# IO_EXPAND.net
KiCad netlist of a schematic drawn in Altium Designer
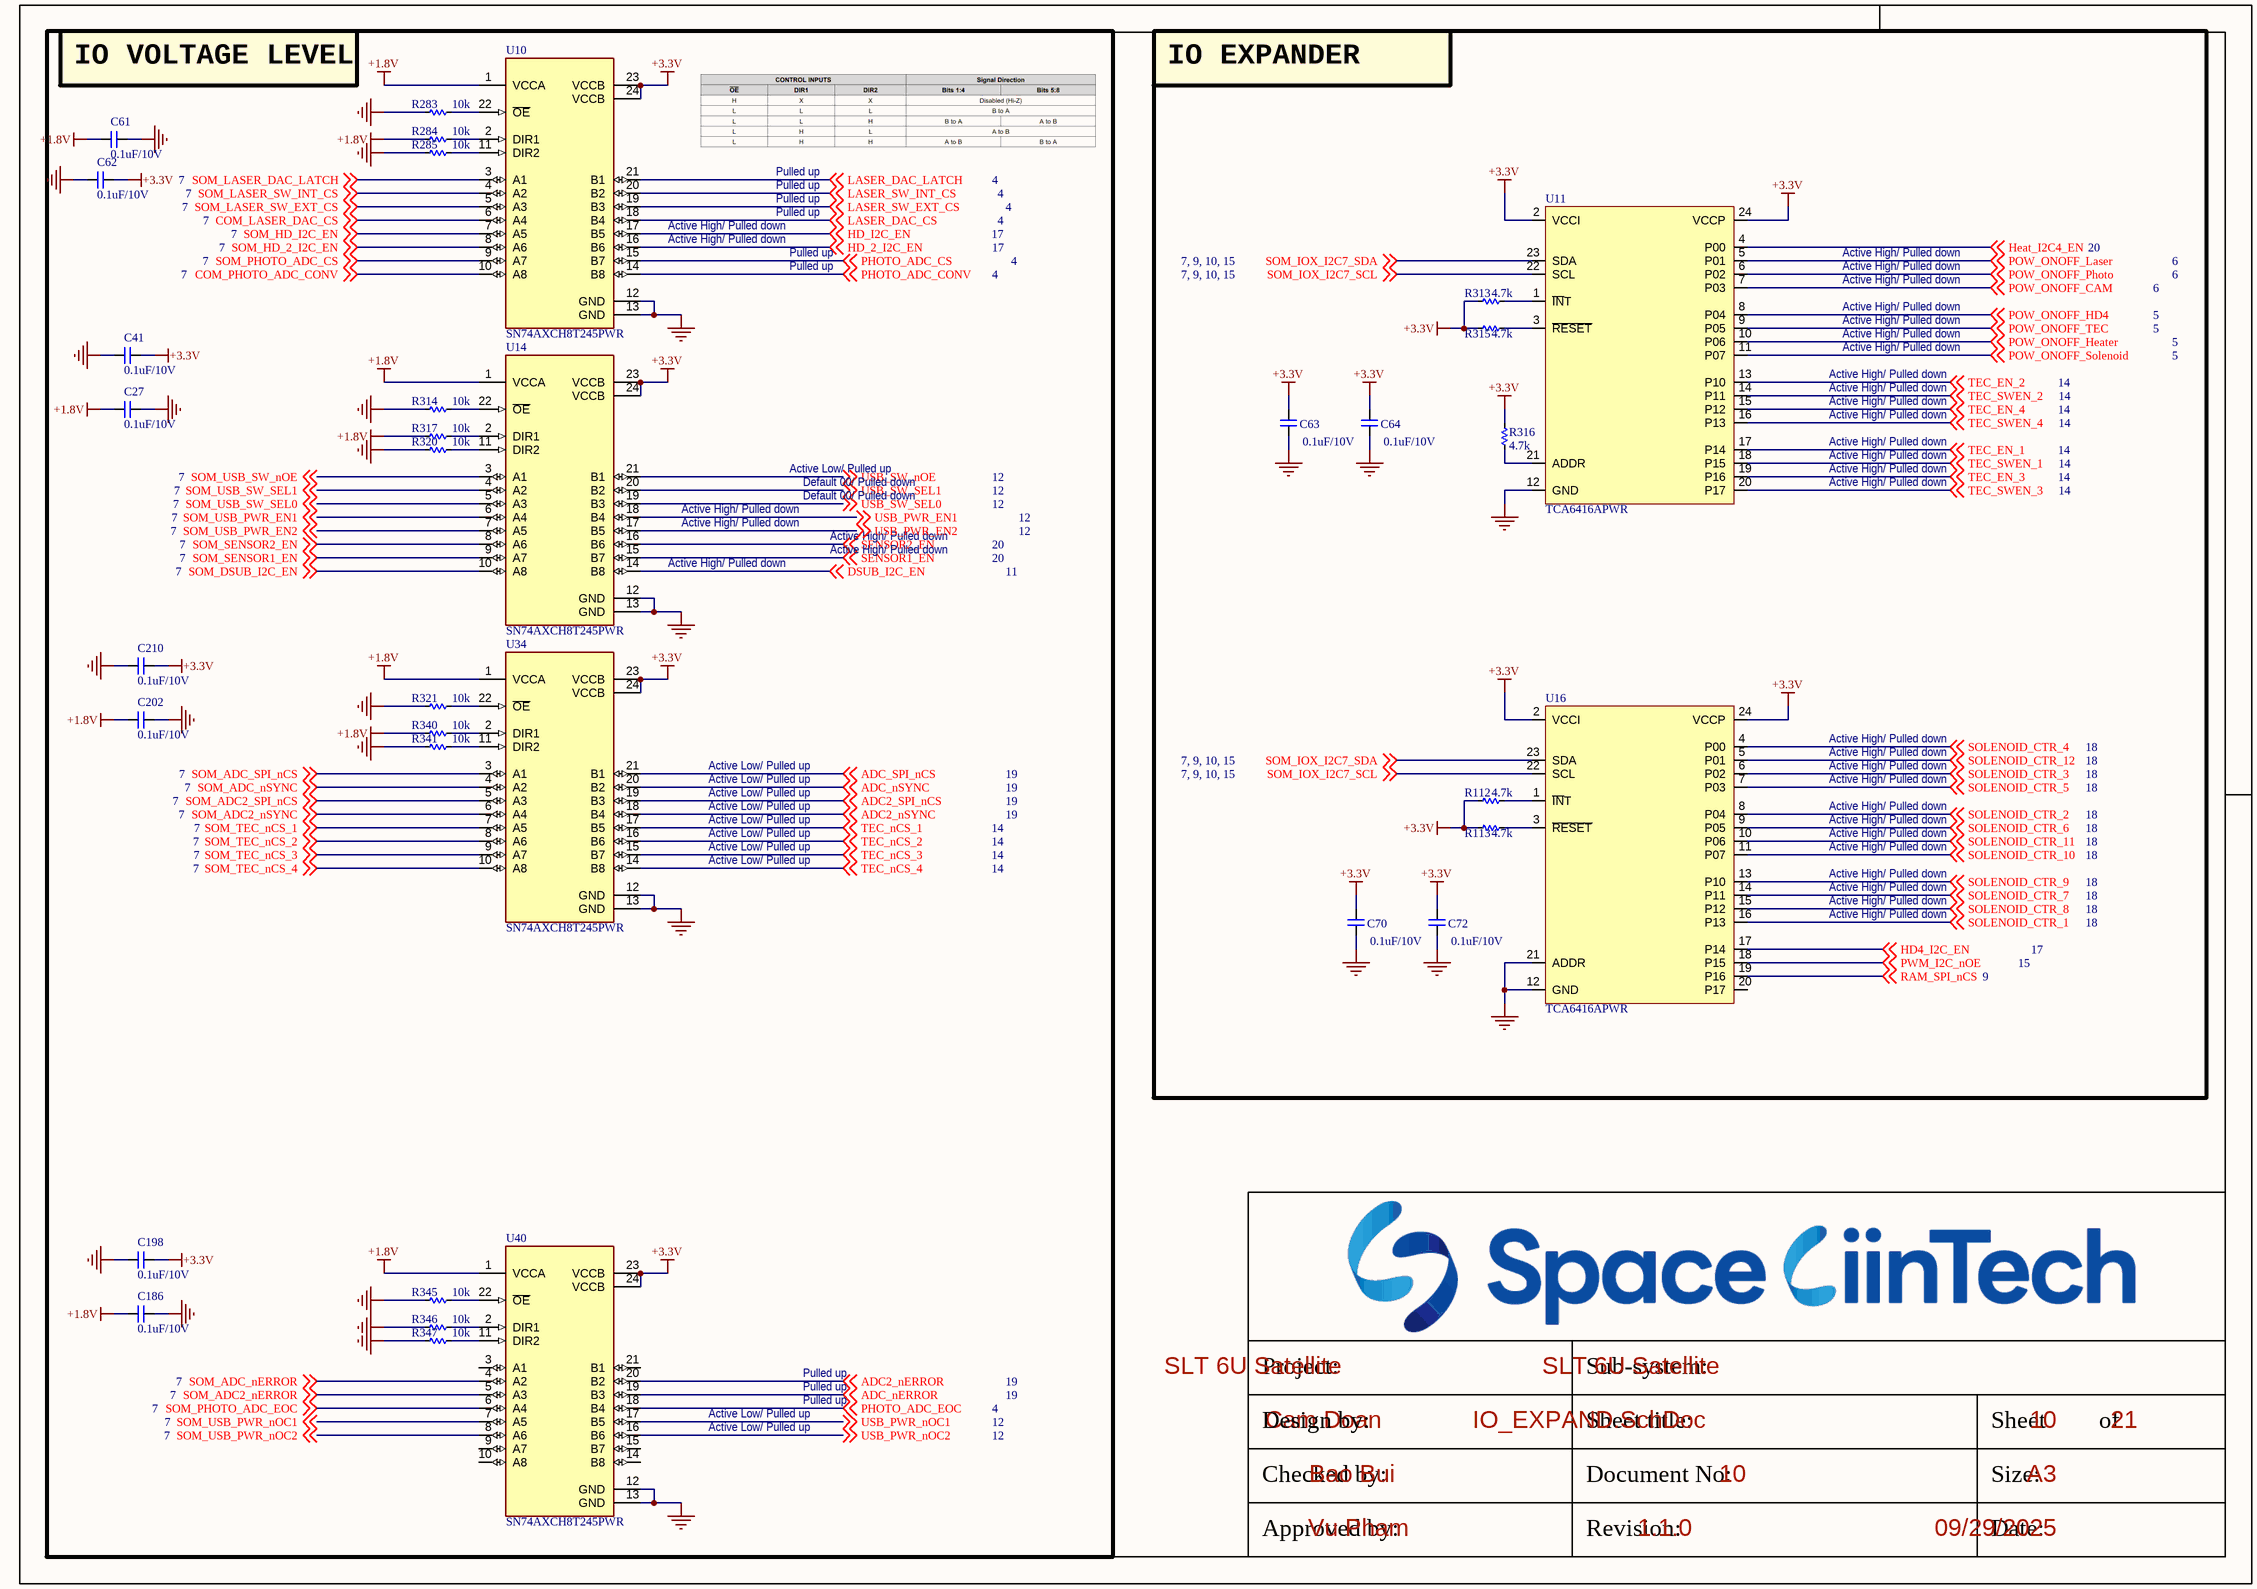
[diagram p0: IO_EXPAND.SchDoc]

(export (version "E")
  (design (tool "Eeschema 10.0.6"))
  (components
    (comp (ref "C27")
      (value "0.1uF/10V")
      (footprint "CAP_C_1005X60")
      (description "CAP CHIP")
      (libsource (lib "LABLIB") (part "_CAP_C_2"))
    )
    (comp (ref "C41")
      (value "0.1uF/10V")
      (footprint "CAP_C_1005X60")
      (description "CAP CHIP")
      (libsource (lib "LABLIB") (part "_CAP_C_2"))
    )
    (comp (ref "C61")
      (value "0.1uF/10V")
      (footprint "CAP_C_1005X60")
      (description "CAP CHIP")
      (libsource (lib "LABLIB") (part "_CAP_C_2"))
    )
    (comp (ref "C62")
      (value "0.1uF/10V")
      (footprint "CAP_C_1005X60")
      (description "CAP CHIP")
      (libsource (lib "LABLIB") (part "_CAP_C_2"))
    )
    (comp (ref "C63")
      (value "0.1uF/10V")
      (footprint "CAP_C_1005X60")
      (description "CAP CHIP")
      (libsource (lib "LABLIB") (part "_CAP_C_2"))
    )
    (comp (ref "C64")
      (value "0.1uF/10V")
      (footprint "CAP_C_1005X60")
      (description "CAP CHIP")
      (libsource (lib "LABLIB") (part "_CAP_C_2"))
    )
    (comp (ref "C70")
      (value "0.1uF/10V")
      (footprint "CAP_C_1005X60")
      (description "CAP CHIP")
      (libsource (lib "LABLIB") (part "_CAP_C_2"))
    )
    (comp (ref "C72")
      (value "0.1uF/10V")
      (footprint "CAP_C_1005X60")
      (description "CAP CHIP")
      (libsource (lib "LABLIB") (part "_CAP_C_2"))
    )
    (comp (ref "C186")
      (value "0.1uF/10V")
      (footprint "CAP_C_1005X60")
      (description "CAP CHIP")
      (libsource (lib "LABLIB") (part "_CAP_C_2"))
    )
    (comp (ref "C198")
      (value "0.1uF/10V")
      (footprint "CAP_C_1005X60")
      (description "CAP CHIP")
      (libsource (lib "LABLIB") (part "_CAP_C_2"))
    )
    (comp (ref "C202")
      (value "0.1uF/10V")
      (footprint "CAP_C_1005X60")
      (description "CAP CHIP")
      (libsource (lib "LABLIB") (part "_CAP_C_2"))
    )
    (comp (ref "C210")
      (value "0.1uF/10V")
      (footprint "CAP_C_1005X60")
      (description "CAP CHIP")
      (libsource (lib "LABLIB") (part "_CAP_C_2"))
    )
    (comp (ref "R112")
      (value "4.7k")
      (footprint "RES_C_1005X40")
      (description "RES")
      (libsource (lib "LABLIB") (part "_RES_B_2"))
    )
    (comp (ref "R113")
      (value "4.7k")
      (footprint "RES_C_1005X40")
      (description "RES")
      (libsource (lib "LABLIB") (part "_RES_B_2"))
    )
    (comp (ref "R283")
      (value "10k")
      (footprint "RES_C_1005X40")
      (description "RES")
      (libsource (lib "LABLIB") (part "_RES_B_2"))
    )
    (comp (ref "R284")
      (value "10k")
      (footprint "RES_C_1005X40")
      (description "RES")
      (libsource (lib "LABLIB") (part "_RES_B_2"))
    )
    (comp (ref "R285")
      (value "10k")
      (footprint "RES_C_1005X40")
      (description "RES")
      (libsource (lib "LABLIB") (part "_RES_B_2"))
    )
    (comp (ref "R313")
      (value "4.7k")
      (footprint "RES_C_1005X40")
      (description "RES")
      (libsource (lib "LABLIB") (part "_RES_B_2"))
    )
    (comp (ref "R314")
      (value "10k")
      (footprint "RES_C_1005X40")
      (description "RES")
      (libsource (lib "LABLIB") (part "_RES_B_2"))
    )
    (comp (ref "R315")
      (value "4.7k")
      (footprint "RES_C_1005X40")
      (description "RES")
      (libsource (lib "LABLIB") (part "_RES_B_2"))
    )
    (comp (ref "R316")
      (value "4.7k")
      (footprint "RES_C_1005X40")
      (description "RES")
      (libsource (lib "LABLIB") (part "_RES_B_2"))
    )
    (comp (ref "R317")
      (value "10k")
      (footprint "RES_C_1005X40")
      (description "RES")
      (libsource (lib "LABLIB") (part "_RES_B_2"))
    )
    (comp (ref "R320")
      (value "10k")
      (footprint "RES_C_1005X40")
      (description "RES")
      (libsource (lib "LABLIB") (part "_RES_B_2"))
    )
    (comp (ref "R321")
      (value "10k")
      (footprint "RES_C_1005X40")
      (description "RES")
      (libsource (lib "LABLIB") (part "_RES_B_2"))
    )
    (comp (ref "R340")
      (value "10k")
      (footprint "RES_C_1005X40")
      (description "RES")
      (libsource (lib "LABLIB") (part "_RES_B_2"))
    )
    (comp (ref "R341")
      (value "10k")
      (footprint "RES_C_1005X40")
      (description "RES")
      (libsource (lib "LABLIB") (part "_RES_B_2"))
    )
    (comp (ref "R345")
      (value "10k")
      (footprint "RES_C_1005X40")
      (description "RES")
      (libsource (lib "LABLIB") (part "_RES_B_2"))
    )
    (comp (ref "R346")
      (value "10k")
      (footprint "RES_C_1005X40")
      (description "RES")
      (libsource (lib "LABLIB") (part "_RES_B_2"))
    )
    (comp (ref "R347")
      (value "10k")
      (footprint "RES_C_1005X40")
      (description "RES")
      (libsource (lib "LABLIB") (part "_RES_B_2"))
    )
    (comp (ref "U10")
      (value "SN74AXCH8T245PWR")
      (footprint "SOP65P640X120-24N")
      (description "8-Bit Dual-Supply Bus Transceiver")
      (fields (field (name "MF") "Texas Instruments"))
      (libsource (lib "LABLIB") (part "IC_voltage_level_SN74AXCH8T245PWR"))
    )
    (comp (ref "U11")
      (value "TCA6416APWR")
      (footprint "SOP65P440W-24N")
      (libsource (lib "CAMERA_SchLib") (part "IC_I2Cto16IO_TCA6416APWR"))
    )
    (comp (ref "U14")
      (value "SN74AXCH8T245PWR")
      (footprint "SOP65P640X120-24N")
      (description "8-Bit Dual-Supply Bus Transceiver")
      (fields (field (name "MF") "Texas Instruments"))
      (libsource (lib "LABLIB") (part "IC_voltage_level_SN74AXCH8T245PWR"))
    )
    (comp (ref "U16")
      (value "TCA6416APWR")
      (footprint "SOP65P440W-24N")
      (libsource (lib "CAMERA_SchLib") (part "IC_I2Cto16IO_TCA6416APWR"))
    )
    (comp (ref "U34")
      (value "SN74AXCH8T245PWR")
      (footprint "SOP65P640X120-24N")
      (description "8-Bit Dual-Supply Bus Transceiver")
      (fields (field (name "MF") "Texas Instruments"))
      (libsource (lib "LABLIB") (part "IC_voltage_level_SN74AXCH8T245PWR"))
    )
    (comp (ref "U40")
      (value "SN74AXCH8T245PWR")
      (footprint "SOP65P640X120-24N")
      (description "8-Bit Dual-Supply Bus Transceiver")
      (fields (field (name "MF") "Texas Instruments"))
      (libsource (lib "LABLIB") (part "IC_voltage_level_SN74AXCH8T245PWR"))
    )
  )
  (nets
    (net (code "1") (name "+1.8V") (class "Default")
      (node (ref "C186") (pin "2") (pinfunction "2_2") (pintype "passive"))
      (node (ref "C202") (pin "2") (pinfunction "2_2") (pintype "passive"))
      (node (ref "C27") (pin "2") (pinfunction "2_2") (pintype "passive"))
      (node (ref "C61") (pin "2") (pinfunction "2_2") (pintype "passive"))
      (node (ref "R284") (pin "2") (pinfunction "2_2") (pintype "passive"))
      (node (ref "R317") (pin "2") (pinfunction "2_2") (pintype "passive"))
      (node (ref "R340") (pin "2") (pinfunction "2_2") (pintype "passive"))
      (node (ref "U10") (pin "1") (pinfunction "VCCA_1") (pintype "power_in"))
      (node (ref "U14") (pin "1") (pinfunction "VCCA_1") (pintype "power_in"))
      (node (ref "U34") (pin "1") (pinfunction "VCCA_1") (pintype "power_in"))
      (node (ref "U40") (pin "1") (pinfunction "VCCA_1") (pintype "power_in"))
    )
    (net (code "2") (name "+3.3V") (class "Default")
      (node (ref "C198") (pin "2") (pinfunction "2_2") (pintype "passive"))
      (node (ref "C210") (pin "2") (pinfunction "2_2") (pintype "passive"))
      (node (ref "C41") (pin "2") (pinfunction "2_2") (pintype "passive"))
      (node (ref "C62") (pin "2") (pinfunction "2_2") (pintype "passive"))
      (node (ref "C63") (pin "2") (pinfunction "2_2") (pintype "passive"))
      (node (ref "C64") (pin "2") (pinfunction "2_2") (pintype "passive"))
      (node (ref "C70") (pin "2") (pinfunction "2_2") (pintype "passive"))
      (node (ref "C72") (pin "2") (pinfunction "2_2") (pintype "passive"))
      (node (ref "R112") (pin "1") (pinfunction "1_1") (pintype "passive"))
      (node (ref "R113") (pin "1") (pinfunction "1_1") (pintype "passive"))
      (node (ref "R313") (pin "1") (pinfunction "1_1") (pintype "passive"))
      (node (ref "R315") (pin "1") (pinfunction "1_1") (pintype "passive"))
      (node (ref "R316") (pin "2") (pinfunction "2_2") (pintype "passive"))
      (node (ref "U10") (pin "23") (pinfunction "VCCB_23") (pintype "power_in"))
      (node (ref "U10") (pin "24") (pinfunction "VCCB_24") (pintype "power_in"))
      (node (ref "U11") (pin "2") (pinfunction "VCCI_2") (pintype "passive"))
      (node (ref "U11") (pin "24") (pinfunction "VCCP_24") (pintype "passive"))
      (node (ref "U14") (pin "23") (pinfunction "VCCB_23") (pintype "power_in"))
      (node (ref "U14") (pin "24") (pinfunction "VCCB_24") (pintype "power_in"))
      (node (ref "U16") (pin "2") (pinfunction "VCCI_2") (pintype "passive"))
      (node (ref "U16") (pin "24") (pinfunction "VCCP_24") (pintype "passive"))
      (node (ref "U34") (pin "23") (pinfunction "VCCB_23") (pintype "power_in"))
      (node (ref "U34") (pin "24") (pinfunction "VCCB_24") (pintype "power_in"))
      (node (ref "U40") (pin "23") (pinfunction "VCCB_23") (pintype "power_in"))
      (node (ref "U40") (pin "24") (pinfunction "VCCB_24") (pintype "power_in"))
    )
    (net (code "3") (name "ADC2_SPI_nCS") (class "Default")
      (node (ref "U34") (pin "19") (pinfunction "B3_19") (pintype "bidirectional"))
    )
    (net (code "4") (name "ADC2_nERROR") (class "Default")
      (node (ref "U40") (pin "20") (pinfunction "B2_20") (pintype "bidirectional"))
    )
    (net (code "5") (name "ADC2_nSYNC") (class "Default")
      (node (ref "U34") (pin "18") (pinfunction "B4_18") (pintype "bidirectional"))
    )
    (net (code "6") (name "ADC_SPI_nCS") (class "Default")
      (node (ref "U34") (pin "21") (pinfunction "B1_21") (pintype "bidirectional"))
    )
    (net (code "7") (name "ADC_nERROR") (class "Default")
      (node (ref "U40") (pin "19") (pinfunction "B3_19") (pintype "bidirectional"))
    )
    (net (code "8") (name "ADC_nSYNC") (class "Default")
      (node (ref "U34") (pin "20") (pinfunction "B2_20") (pintype "bidirectional"))
    )
    (net (code "9") (name "COM_LASER_DAC_CS") (class "Default")
      (node (ref "U10") (pin "6") (pinfunction "A4_6") (pintype "bidirectional"))
    )
    (net (code "10") (name "COM_PHOTO_ADC_CONV") (class "Default")
      (node (ref "U10") (pin "10") (pinfunction "A8_10") (pintype "bidirectional"))
    )
    (net (code "11") (name "DSUB_I2C_EN") (class "Default")
      (node (ref "U14") (pin "14") (pinfunction "B8_14") (pintype "bidirectional"))
    )
    (net (code "12") (name "GND") (class "Default")
      (node (ref "C186") (pin "1") (pinfunction "1_1") (pintype "passive"))
      (node (ref "C198") (pin "1") (pinfunction "1_1") (pintype "passive"))
      (node (ref "C202") (pin "1") (pinfunction "1_1") (pintype "passive"))
      (node (ref "C210") (pin "1") (pinfunction "1_1") (pintype "passive"))
      (node (ref "C27") (pin "1") (pinfunction "1_1") (pintype "passive"))
      (node (ref "C41") (pin "1") (pinfunction "1_1") (pintype "passive"))
      (node (ref "C61") (pin "1") (pinfunction "1_1") (pintype "passive"))
      (node (ref "C62") (pin "1") (pinfunction "1_1") (pintype "passive"))
      (node (ref "C63") (pin "1") (pinfunction "1_1") (pintype "passive"))
      (node (ref "C64") (pin "1") (pinfunction "1_1") (pintype "passive"))
      (node (ref "C70") (pin "1") (pinfunction "1_1") (pintype "passive"))
      (node (ref "C72") (pin "1") (pinfunction "1_1") (pintype "passive"))
      (node (ref "R283") (pin "2") (pinfunction "2_2") (pintype "passive"))
      (node (ref "R285") (pin "2") (pinfunction "2_2") (pintype "passive"))
      (node (ref "R314") (pin "2") (pinfunction "2_2") (pintype "passive"))
      (node (ref "R320") (pin "2") (pinfunction "2_2") (pintype "passive"))
      (node (ref "R321") (pin "2") (pinfunction "2_2") (pintype "passive"))
      (node (ref "R341") (pin "2") (pinfunction "2_2") (pintype "passive"))
      (node (ref "R345") (pin "2") (pinfunction "2_2") (pintype "passive"))
      (node (ref "R346") (pin "2") (pinfunction "2_2") (pintype "passive"))
      (node (ref "R347") (pin "2") (pinfunction "2_2") (pintype "passive"))
      (node (ref "U10") (pin "12") (pinfunction "GND_12") (pintype "power_in"))
      (node (ref "U10") (pin "13") (pinfunction "GND_13") (pintype "power_in"))
      (node (ref "U11") (pin "12") (pinfunction "GND_12") (pintype "passive"))
      (node (ref "U14") (pin "12") (pinfunction "GND_12") (pintype "power_in"))
      (node (ref "U14") (pin "13") (pinfunction "GND_13") (pintype "power_in"))
      (node (ref "U16") (pin "12") (pinfunction "GND_12") (pintype "passive"))
      (node (ref "U16") (pin "21") (pinfunction "ADDR_21") (pintype "passive"))
      (node (ref "U34") (pin "12") (pinfunction "GND_12") (pintype "power_in"))
      (node (ref "U34") (pin "13") (pinfunction "GND_13") (pintype "power_in"))
      (node (ref "U40") (pin "12") (pinfunction "GND_12") (pintype "power_in"))
      (node (ref "U40") (pin "13") (pinfunction "GND_13") (pintype "power_in"))
    )
    (net (code "13") (name "HD4_I2C_EN") (class "Default")
      (node (ref "U16") (pin "17") (pinfunction "P14_17") (pintype "passive"))
    )
    (net (code "14") (name "HD_2_I2C_EN") (class "Default")
      (node (ref "U10") (pin "16") (pinfunction "B6_16") (pintype "bidirectional"))
    )
    (net (code "15") (name "HD_I2C_EN") (class "Default")
      (node (ref "U10") (pin "17") (pinfunction "B5_17") (pintype "bidirectional"))
    )
    (net (code "16") (name "Heat_I2C4_EN") (class "Default")
      (node (ref "U11") (pin "4") (pinfunction "P00_4") (pintype "passive"))
    )
    (net (code "17") (name "LASER_DAC_CS") (class "Default")
      (node (ref "U10") (pin "18") (pinfunction "B4_18") (pintype "bidirectional"))
    )
    (net (code "18") (name "LASER_DAC_LATCH") (class "Default")
      (node (ref "U10") (pin "21") (pinfunction "B1_21") (pintype "bidirectional"))
    )
    (net (code "19") (name "LASER_SW_EXT_CS") (class "Default")
      (node (ref "U10") (pin "19") (pinfunction "B3_19") (pintype "bidirectional"))
    )
    (net (code "20") (name "LASER_SW_INT_CS") (class "Default")
      (node (ref "U10") (pin "20") (pinfunction "B2_20") (pintype "bidirectional"))
    )
    (net (code "21") (name "Net-(U10-DIR1)") (class "Default")
      (node (ref "R284") (pin "1") (pinfunction "1_1") (pintype "passive"))
      (node (ref "U10") (pin "2") (pinfunction "DIR1_2") (pintype "input"))
    )
    (net (code "22") (name "Net-(U10-DIR2)") (class "Default")
      (node (ref "R285") (pin "1") (pinfunction "1_1") (pintype "passive"))
      (node (ref "U10") (pin "11") (pinfunction "DIR2_11") (pintype "input"))
    )
    (net (code "23") (name "Net-(U10-~{OE})") (class "Default")
      (node (ref "R283") (pin "1") (pinfunction "1_1") (pintype "passive"))
      (node (ref "U10") (pin "22") (pinfunction "~{OE}_22") (pintype "input"))
    )
    (net (code "24") (name "Net-(U11-ADDR)") (class "Default")
      (node (ref "R316") (pin "1") (pinfunction "1_1") (pintype "passive"))
      (node (ref "U11") (pin "21") (pinfunction "ADDR_21") (pintype "passive"))
    )
    (net (code "25") (name "Net-(U11-~{IN}T)") (class "Default")
      (node (ref "R313") (pin "2") (pinfunction "2_2") (pintype "passive"))
      (node (ref "U11") (pin "1") (pinfunction "~{IN}T_1") (pintype "passive"))
    )
    (net (code "26") (name "Net-(U11-~{RESET})") (class "Default")
      (node (ref "R315") (pin "2") (pinfunction "2_2") (pintype "passive"))
      (node (ref "U11") (pin "3") (pinfunction "~{RESET}_3") (pintype "passive"))
    )
    (net (code "27") (name "Net-(U14-DIR1)") (class "Default")
      (node (ref "R317") (pin "1") (pinfunction "1_1") (pintype "passive"))
      (node (ref "U14") (pin "2") (pinfunction "DIR1_2") (pintype "input"))
    )
    (net (code "28") (name "Net-(U14-DIR2)") (class "Default")
      (node (ref "R320") (pin "1") (pinfunction "1_1") (pintype "passive"))
      (node (ref "U14") (pin "11") (pinfunction "DIR2_11") (pintype "input"))
    )
    (net (code "29") (name "Net-(U14-~{OE})") (class "Default")
      (node (ref "R314") (pin "1") (pinfunction "1_1") (pintype "passive"))
      (node (ref "U14") (pin "22") (pinfunction "~{OE}_22") (pintype "input"))
    )
    (net (code "30") (name "Net-(U16-~{IN}T)") (class "Default")
      (node (ref "R112") (pin "2") (pinfunction "2_2") (pintype "passive"))
      (node (ref "U16") (pin "1") (pinfunction "~{IN}T_1") (pintype "passive"))
    )
    (net (code "31") (name "Net-(U16-~{RESET})") (class "Default")
      (node (ref "R113") (pin "2") (pinfunction "2_2") (pintype "passive"))
      (node (ref "U16") (pin "3") (pinfunction "~{RESET}_3") (pintype "passive"))
    )
    (net (code "32") (name "Net-(U34-DIR1)") (class "Default")
      (node (ref "R340") (pin "1") (pinfunction "1_1") (pintype "passive"))
      (node (ref "U34") (pin "2") (pinfunction "DIR1_2") (pintype "input"))
    )
    (net (code "33") (name "Net-(U34-DIR2)") (class "Default")
      (node (ref "R341") (pin "1") (pinfunction "1_1") (pintype "passive"))
      (node (ref "U34") (pin "11") (pinfunction "DIR2_11") (pintype "input"))
    )
    (net (code "34") (name "Net-(U34-~{OE})") (class "Default")
      (node (ref "R321") (pin "1") (pinfunction "1_1") (pintype "passive"))
      (node (ref "U34") (pin "22") (pinfunction "~{OE}_22") (pintype "input"))
    )
    (net (code "35") (name "Net-(U40-DIR1)") (class "Default")
      (node (ref "R346") (pin "1") (pinfunction "1_1") (pintype "passive"))
      (node (ref "U40") (pin "2") (pinfunction "DIR1_2") (pintype "input"))
    )
    (net (code "36") (name "Net-(U40-DIR2)") (class "Default")
      (node (ref "R347") (pin "1") (pinfunction "1_1") (pintype "passive"))
      (node (ref "U40") (pin "11") (pinfunction "DIR2_11") (pintype "input"))
    )
    (net (code "37") (name "Net-(U40-~{OE})") (class "Default")
      (node (ref "R345") (pin "1") (pinfunction "1_1") (pintype "passive"))
      (node (ref "U40") (pin "22") (pinfunction "~{OE}_22") (pintype "input"))
    )
    (net (code "38") (name "PHOTO_ADC_CONV") (class "Default")
      (node (ref "U10") (pin "14") (pinfunction "B8_14") (pintype "bidirectional"))
    )
    (net (code "39") (name "PHOTO_ADC_CS") (class "Default")
      (node (ref "U10") (pin "15") (pinfunction "B7_15") (pintype "bidirectional"))
    )
    (net (code "40") (name "PHOTO_ADC_EOC") (class "Default")
      (node (ref "U40") (pin "18") (pinfunction "B4_18") (pintype "bidirectional"))
    )
    (net (code "41") (name "POW_ONOFF_CAM") (class "Default")
      (node (ref "U11") (pin "7") (pinfunction "P03_7") (pintype "passive"))
    )
    (net (code "42") (name "POW_ONOFF_HD4") (class "Default")
      (node (ref "U11") (pin "8") (pinfunction "P04_8") (pintype "passive"))
    )
    (net (code "43") (name "POW_ONOFF_Heater") (class "Default")
      (node (ref "U11") (pin "10") (pinfunction "P06_10") (pintype "passive"))
    )
    (net (code "44") (name "POW_ONOFF_Laser") (class "Default")
      (node (ref "U11") (pin "5") (pinfunction "P01_5") (pintype "passive"))
    )
    (net (code "45") (name "POW_ONOFF_Photo") (class "Default")
      (node (ref "U11") (pin "6") (pinfunction "P02_6") (pintype "passive"))
    )
    (net (code "46") (name "POW_ONOFF_Solenoid") (class "Default")
      (node (ref "U11") (pin "11") (pinfunction "P07_11") (pintype "passive"))
    )
    (net (code "47") (name "POW_ONOFF_TEC") (class "Default")
      (node (ref "U11") (pin "9") (pinfunction "P05_9") (pintype "passive"))
    )
    (net (code "48") (name "PWM_I2C_nOE") (class "Default")
      (node (ref "U16") (pin "18") (pinfunction "P15_18") (pintype "passive"))
    )
    (net (code "49") (name "RAM_SPI_nCS") (class "Default")
      (node (ref "U16") (pin "19") (pinfunction "P16_19") (pintype "passive"))
    )
    (net (code "50") (name "SENSOR1_EN") (class "Default")
      (node (ref "U14") (pin "15") (pinfunction "B7_15") (pintype "bidirectional"))
    )
    (net (code "51") (name "SENSOR2_EN") (class "Default")
      (node (ref "U14") (pin "16") (pinfunction "B6_16") (pintype "bidirectional"))
    )
    (net (code "52") (name "SOLENOID_CTR_1") (class "Default")
      (node (ref "U16") (pin "16") (pinfunction "P13_16") (pintype "passive"))
    )
    (net (code "53") (name "SOLENOID_CTR_2") (class "Default")
      (node (ref "U16") (pin "8") (pinfunction "P04_8") (pintype "passive"))
    )
    (net (code "54") (name "SOLENOID_CTR_3") (class "Default")
      (node (ref "U16") (pin "6") (pinfunction "P02_6") (pintype "passive"))
    )
    (net (code "55") (name "SOLENOID_CTR_4") (class "Default")
      (node (ref "U16") (pin "4") (pinfunction "P00_4") (pintype "passive"))
    )
    (net (code "56") (name "SOLENOID_CTR_5") (class "Default")
      (node (ref "U16") (pin "7") (pinfunction "P03_7") (pintype "passive"))
    )
    (net (code "57") (name "SOLENOID_CTR_6") (class "Default")
      (node (ref "U16") (pin "9") (pinfunction "P05_9") (pintype "passive"))
    )
    (net (code "58") (name "SOLENOID_CTR_7") (class "Default")
      (node (ref "U16") (pin "14") (pinfunction "P11_14") (pintype "passive"))
    )
    (net (code "59") (name "SOLENOID_CTR_8") (class "Default")
      (node (ref "U16") (pin "15") (pinfunction "P12_15") (pintype "passive"))
    )
    (net (code "60") (name "SOLENOID_CTR_9") (class "Default")
      (node (ref "U16") (pin "13") (pinfunction "P10_13") (pintype "passive"))
    )
    (net (code "61") (name "SOLENOID_CTR_10") (class "Default")
      (node (ref "U16") (pin "11") (pinfunction "P07_11") (pintype "passive"))
    )
    (net (code "62") (name "SOLENOID_CTR_11") (class "Default")
      (node (ref "U16") (pin "10") (pinfunction "P06_10") (pintype "passive"))
    )
    (net (code "63") (name "SOLENOID_CTR_12") (class "Default")
      (node (ref "U16") (pin "5") (pinfunction "P01_5") (pintype "passive"))
    )
    (net (code "64") (name "SOM_ADC2_SPI_nCS") (class "Default")
      (node (ref "U34") (pin "5") (pinfunction "A3_5") (pintype "bidirectional"))
    )
    (net (code "65") (name "SOM_ADC2_nERROR") (class "Default")
      (node (ref "U40") (pin "5") (pinfunction "A3_5") (pintype "bidirectional"))
    )
    (net (code "66") (name "SOM_ADC2_nSYNC") (class "Default")
      (node (ref "U34") (pin "6") (pinfunction "A4_6") (pintype "bidirectional"))
    )
    (net (code "67") (name "SOM_ADC_SPI_nCS") (class "Default")
      (node (ref "U34") (pin "3") (pinfunction "A1_3") (pintype "bidirectional"))
    )
    (net (code "68") (name "SOM_ADC_nERROR") (class "Default")
      (node (ref "U40") (pin "4") (pinfunction "A2_4") (pintype "bidirectional"))
    )
    (net (code "69") (name "SOM_ADC_nSYNC") (class "Default")
      (node (ref "U34") (pin "4") (pinfunction "A2_4") (pintype "bidirectional"))
    )
    (net (code "70") (name "SOM_DSUB_I2C_EN") (class "Default")
      (node (ref "U14") (pin "10") (pinfunction "A8_10") (pintype "bidirectional"))
    )
    (net (code "71") (name "SOM_HD_2_I2C_EN") (class "Default")
      (node (ref "U10") (pin "8") (pinfunction "A6_8") (pintype "bidirectional"))
    )
    (net (code "72") (name "SOM_HD_I2C_EN") (class "Default")
      (node (ref "U10") (pin "7") (pinfunction "A5_7") (pintype "bidirectional"))
    )
    (net (code "73") (name "SOM_IOX_I2C7_SCL") (class "Default")
      (node (ref "U11") (pin "22") (pinfunction "SCL_22") (pintype "passive"))
      (node (ref "U16") (pin "22") (pinfunction "SCL_22") (pintype "passive"))
    )
    (net (code "74") (name "SOM_IOX_I2C7_SDA") (class "Default")
      (node (ref "U11") (pin "23") (pinfunction "SDA_23") (pintype "passive"))
      (node (ref "U16") (pin "23") (pinfunction "SDA_23") (pintype "passive"))
    )
    (net (code "75") (name "SOM_LASER_DAC_LATCH") (class "Default")
      (node (ref "U10") (pin "3") (pinfunction "A1_3") (pintype "bidirectional"))
    )
    (net (code "76") (name "SOM_LASER_SW_EXT_CS") (class "Default")
      (node (ref "U10") (pin "5") (pinfunction "A3_5") (pintype "bidirectional"))
    )
    (net (code "77") (name "SOM_LASER_SW_INT_CS") (class "Default")
      (node (ref "U10") (pin "4") (pinfunction "A2_4") (pintype "bidirectional"))
    )
    (net (code "78") (name "SOM_PHOTO_ADC_CS") (class "Default")
      (node (ref "U10") (pin "9") (pinfunction "A7_9") (pintype "bidirectional"))
    )
    (net (code "79") (name "SOM_PHOTO_ADC_EOC") (class "Default")
      (node (ref "U40") (pin "6") (pinfunction "A4_6") (pintype "bidirectional"))
    )
    (net (code "80") (name "SOM_SENSOR1_EN") (class "Default")
      (node (ref "U14") (pin "9") (pinfunction "A7_9") (pintype "bidirectional"))
    )
    (net (code "81") (name "SOM_SENSOR2_EN") (class "Default")
      (node (ref "U14") (pin "8") (pinfunction "A6_8") (pintype "bidirectional"))
    )
    (net (code "82") (name "SOM_TEC_nCS_1") (class "Default")
      (node (ref "U34") (pin "7") (pinfunction "A5_7") (pintype "bidirectional"))
    )
    (net (code "83") (name "SOM_TEC_nCS_2") (class "Default")
      (node (ref "U34") (pin "8") (pinfunction "A6_8") (pintype "bidirectional"))
    )
    (net (code "84") (name "SOM_TEC_nCS_3") (class "Default")
      (node (ref "U34") (pin "9") (pinfunction "A7_9") (pintype "bidirectional"))
    )
    (net (code "85") (name "SOM_TEC_nCS_4") (class "Default")
      (node (ref "U34") (pin "10") (pinfunction "A8_10") (pintype "bidirectional"))
    )
    (net (code "86") (name "SOM_USB_PWR_EN1") (class "Default")
      (node (ref "U14") (pin "6") (pinfunction "A4_6") (pintype "bidirectional"))
    )
    (net (code "87") (name "SOM_USB_PWR_EN2") (class "Default")
      (node (ref "U14") (pin "7") (pinfunction "A5_7") (pintype "bidirectional"))
    )
    (net (code "88") (name "SOM_USB_PWR_nOC1") (class "Default")
      (node (ref "U40") (pin "7") (pinfunction "A5_7") (pintype "bidirectional"))
    )
    (net (code "89") (name "SOM_USB_PWR_nOC2") (class "Default")
      (node (ref "U40") (pin "8") (pinfunction "A6_8") (pintype "bidirectional"))
    )
    (net (code "90") (name "SOM_USB_SW_SEL0") (class "Default")
      (node (ref "U14") (pin "5") (pinfunction "A3_5") (pintype "bidirectional"))
    )
    (net (code "91") (name "SOM_USB_SW_SEL1") (class "Default")
      (node (ref "U14") (pin "4") (pinfunction "A2_4") (pintype "bidirectional"))
    )
    (net (code "92") (name "SOM_USB_SW_nOE") (class "Default")
      (node (ref "U14") (pin "3") (pinfunction "A1_3") (pintype "bidirectional"))
    )
    (net (code "93") (name "TEC_EN_1") (class "Default")
      (node (ref "U11") (pin "17") (pinfunction "P14_17") (pintype "passive"))
    )
    (net (code "94") (name "TEC_EN_2") (class "Default")
      (node (ref "U11") (pin "13") (pinfunction "P10_13") (pintype "passive"))
    )
    (net (code "95") (name "TEC_EN_3") (class "Default")
      (node (ref "U11") (pin "19") (pinfunction "P16_19") (pintype "passive"))
    )
    (net (code "96") (name "TEC_EN_4") (class "Default")
      (node (ref "U11") (pin "15") (pinfunction "P12_15") (pintype "passive"))
    )
    (net (code "97") (name "TEC_SWEN_1") (class "Default")
      (node (ref "U11") (pin "18") (pinfunction "P15_18") (pintype "passive"))
    )
    (net (code "98") (name "TEC_SWEN_2") (class "Default")
      (node (ref "U11") (pin "14") (pinfunction "P11_14") (pintype "passive"))
    )
    (net (code "99") (name "TEC_SWEN_3") (class "Default")
      (node (ref "U11") (pin "20") (pinfunction "P17_20") (pintype "passive"))
    )
    (net (code "100") (name "TEC_SWEN_4") (class "Default")
      (node (ref "U11") (pin "16") (pinfunction "P13_16") (pintype "passive"))
    )
    (net (code "101") (name "TEC_nCS_1") (class "Default")
      (node (ref "U34") (pin "17") (pinfunction "B5_17") (pintype "bidirectional"))
    )
    (net (code "102") (name "TEC_nCS_2") (class "Default")
      (node (ref "U34") (pin "16") (pinfunction "B6_16") (pintype "bidirectional"))
    )
    (net (code "103") (name "TEC_nCS_3") (class "Default")
      (node (ref "U34") (pin "15") (pinfunction "B7_15") (pintype "bidirectional"))
    )
    (net (code "104") (name "TEC_nCS_4") (class "Default")
      (node (ref "U34") (pin "14") (pinfunction "B8_14") (pintype "bidirectional"))
    )
    (net (code "105") (name "USB_PWR_EN1") (class "Default")
      (node (ref "U14") (pin "18") (pinfunction "B4_18") (pintype "bidirectional"))
    )
    (net (code "106") (name "USB_PWR_EN2") (class "Default")
      (node (ref "U14") (pin "17") (pinfunction "B5_17") (pintype "bidirectional"))
    )
    (net (code "107") (name "USB_PWR_nOC1") (class "Default")
      (node (ref "U40") (pin "17") (pinfunction "B5_17") (pintype "bidirectional"))
    )
    (net (code "108") (name "USB_PWR_nOC2") (class "Default")
      (node (ref "U40") (pin "16") (pinfunction "B6_16") (pintype "bidirectional"))
    )
    (net (code "109") (name "USB_SW_SEL0") (class "Default")
      (node (ref "U14") (pin "19") (pinfunction "B3_19") (pintype "bidirectional"))
    )
    (net (code "110") (name "USB_SW_SEL1") (class "Default")
      (node (ref "U14") (pin "20") (pinfunction "B2_20") (pintype "bidirectional"))
    )
    (net (code "111") (name "USB_SW_nOE") (class "Default")
      (node (ref "U14") (pin "21") (pinfunction "B1_21") (pintype "bidirectional"))
    )
    (net (code "112") (name "unconnected-(U16-P17-Pad20)") (class "Default")
      (node (ref "U16") (pin "20") (pinfunction "P17_20") (pintype "passive"))
    )
    (net (code "113") (name "unconnected-(U40-A1-Pad3)") (class "Default")
      (node (ref "U40") (pin "3") (pinfunction "A1_3") (pintype "bidirectional"))
    )
    (net (code "114") (name "unconnected-(U40-A7-Pad9)") (class "Default")
      (node (ref "U40") (pin "9") (pinfunction "A7_9") (pintype "bidirectional"))
    )
    (net (code "115") (name "unconnected-(U40-A8-Pad10)") (class "Default")
      (node (ref "U40") (pin "10") (pinfunction "A8_10") (pintype "bidirectional"))
    )
    (net (code "116") (name "unconnected-(U40-B1-Pad21)") (class "Default")
      (node (ref "U40") (pin "21") (pinfunction "B1_21") (pintype "bidirectional"))
    )
    (net (code "117") (name "unconnected-(U40-B7-Pad15)") (class "Default")
      (node (ref "U40") (pin "15") (pinfunction "B7_15") (pintype "bidirectional"))
    )
    (net (code "118") (name "unconnected-(U40-B8-Pad14)") (class "Default")
      (node (ref "U40") (pin "14") (pinfunction "B8_14") (pintype "bidirectional"))
    )
  )
)
